# Amplifier_Right.net
KiCad netlist of a schematic drawn in Altium Designer
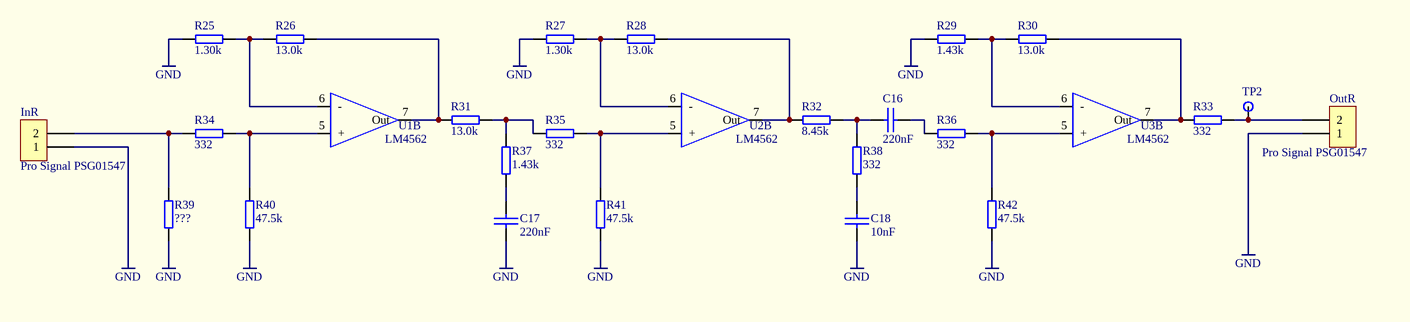
[diagram p0: Amplifier_Right.SchDoc]

(export (version "E")
  (design (tool "Eeschema 10.0.6"))
  (components
    (comp (ref "C16")
      (value "220nF")
      (footprint "CAP_C200-1")
      (description "Capacitor")
      (libsource (lib "*") (part "CAP"))
    )
    (comp (ref "C17")
      (value "220nF")
      (footprint "CAP_C200-1")
      (description "Capacitor")
      (libsource (lib "*") (part "CAP"))
    )
    (comp (ref "C18")
      (value "10nF")
      (footprint "CAP_C200")
      (description "Capacitor")
      (libsource (lib "*") (part "CAP"))
    )
    (comp (ref "InR")
      (value "Pro Signal PSG01547")
      (footprint "CON_RCA_PSG01547")
      (description "Connector")
      (libsource (lib "*") (part "CON2"))
    )
    (comp (ref "OutR")
      (value "Pro Signal PSG01547")
      (footprint "CON_RCA_PSG01547")
      (description "Connector")
      (libsource (lib "") (part "CON2_1"))
    )
    (comp (ref "R25")
      (value "1.30k")
      (footprint "RES_R400")
      (description "Resistor")
      (libsource (lib "MainSchlib") (part "RES"))
    )
    (comp (ref "R26")
      (value "13.0k")
      (footprint "RES_R400")
      (description "Resistor")
      (libsource (lib "MainSchlib") (part "RES"))
    )
    (comp (ref "R27")
      (value "1.30k")
      (footprint "RES_R400")
      (description "Resistor")
      (libsource (lib "MainSchlib") (part "RES"))
    )
    (comp (ref "R28")
      (value "13.0k")
      (footprint "RES_R400")
      (description "Resistor")
      (libsource (lib "MainSchlib") (part "RES"))
    )
    (comp (ref "R29")
      (value "1.43k")
      (footprint "RES_R400")
      (description "Resistor")
      (libsource (lib "MainSchlib") (part "RES"))
    )
    (comp (ref "R30")
      (value "13.0k")
      (footprint "RES_R400")
      (description "Resistor")
      (libsource (lib "MainSchlib") (part "RES"))
    )
    (comp (ref "R31")
      (value "13.0k")
      (footprint "RES_R400")
      (description "Resistor")
      (libsource (lib "MainSchlib") (part "RES"))
    )
    (comp (ref "R32")
      (value "8.45k")
      (footprint "RES_R400")
      (description "Resistor")
      (libsource (lib "MainSchlib") (part "RES"))
    )
    (comp (ref "R33")
      (value "332")
      (footprint "RES_R400")
      (description "Resistor")
      (libsource (lib "MainSchlib") (part "RES"))
    )
    (comp (ref "R34")
      (value "332")
      (footprint "RES_R400")
      (description "Resistor")
      (libsource (lib "MainSchlib") (part "RES"))
    )
    (comp (ref "R35")
      (value "332")
      (footprint "RES_R400")
      (description "Resistor")
      (libsource (lib "MainSchlib") (part "RES"))
    )
    (comp (ref "R36")
      (value "332")
      (footprint "RES_R400")
      (description "Resistor")
      (libsource (lib "MainSchlib") (part "RES"))
    )
    (comp (ref "R37")
      (value "1.43k")
      (footprint "RES_R400")
      (description "Resistor")
      (libsource (lib "MainSchlib") (part "RES"))
    )
    (comp (ref "R38")
      (value "332")
      (footprint "RES_R400")
      (description "Resistor")
      (libsource (lib "MainSchlib") (part "RES"))
    )
    (comp (ref "R39")
      (value "???")
      (footprint "RES_R400")
      (description "Resistor")
      (libsource (lib "MainSchlib") (part "RES"))
    )
    (comp (ref "R40")
      (value "47.5k")
      (footprint "RES_R400")
      (description "Resistor")
      (libsource (lib "MainSchlib") (part "RES"))
    )
    (comp (ref "R41")
      (value "47.5k")
      (footprint "RES_R400")
      (description "Resistor")
      (libsource (lib "MainSchlib") (part "RES"))
    )
    (comp (ref "R42")
      (value "47.5k")
      (footprint "RES_R400")
      (description "Resistor")
      (libsource (lib "MainSchlib") (part "RES"))
    )
    (comp (ref "TP2")
      (value "TESTPAD")
      (footprint "MISC_PAD-36/65")
      (libsource (lib "MainSchlib") (part "TESTPAD"))
    )
    (comp (ref "U1")
      (value "LM4562")
      (footprint "IC_DIP-8")
      (description "standard dual op-amp")
      (libsource (lib "MainSchlib") (part "OPAMP_Dual"))
    )
    (comp (ref "U2")
      (value "LM4562")
      (footprint "IC_DIP-8")
      (description "standard dual op-amp")
      (libsource (lib "MainSchlib") (part "OPAMP_Dual"))
    )
    (comp (ref "U3")
      (value "LM4562")
      (footprint "IC_DIP-8")
      (description "standard dual op-amp")
      (libsource (lib "MainSchlib") (part "OPAMP_Dual"))
    )
  )
  (nets
    (net (code "1") (name "GND") (class "Default")
      (node (ref "C17") (pin "2") (pinfunction "2_2") (pintype "passive"))
      (node (ref "C18") (pin "2") (pinfunction "2_2") (pintype "passive"))
      (node (ref "InR") (pin "1") (pinfunction "1_1") (pintype "passive"))
      (node (ref "OutR") (pin "1") (pinfunction "1_1") (pintype "passive"))
      (node (ref "R25") (pin "2") (pintype "passive"))
      (node (ref "R27") (pin "2") (pintype "passive"))
      (node (ref "R29") (pin "2") (pintype "passive"))
      (node (ref "R39") (pin "1") (pintype "passive"))
      (node (ref "R40") (pin "2") (pintype "passive"))
      (node (ref "R41") (pin "2") (pintype "passive"))
      (node (ref "R42") (pin "2") (pintype "passive"))
    )
    (net (code "2") (name "Net-(C16-Pad1)") (class "Default")
      (node (ref "C16") (pin "1") (pinfunction "1_1") (pintype "passive"))
      (node (ref "R32") (pin "1") (pintype "passive"))
      (node (ref "R38") (pin "1") (pintype "passive"))
    )
    (net (code "3") (name "Net-(C16-Pad2)") (class "Default")
      (node (ref "C16") (pin "2") (pinfunction "2_2") (pintype "passive"))
      (node (ref "R36") (pin "2") (pintype "passive"))
    )
    (net (code "4") (name "Net-(C17-Pad1)") (class "Default")
      (node (ref "C17") (pin "1") (pinfunction "1_1") (pintype "passive"))
      (node (ref "R37") (pin "2") (pintype "passive"))
    )
    (net (code "5") (name "Net-(C18-Pad1)") (class "Default")
      (node (ref "C18") (pin "1") (pinfunction "1_1") (pintype "passive"))
      (node (ref "R38") (pin "2") (pintype "passive"))
    )
    (net (code "6") (name "Net-(InR-Pad2)") (class "Default")
      (node (ref "InR") (pin "2") (pinfunction "2_2") (pintype "passive"))
      (node (ref "R34") (pin "2") (pintype "passive"))
      (node (ref "R39") (pin "2") (pintype "passive"))
    )
    (net (code "7") (name "Net-(OutR-Pad2)") (class "Default")
      (node (ref "OutR") (pin "2") (pinfunction "2_2") (pintype "passive"))
      (node (ref "R33") (pin "1") (pintype "passive"))
      (node (ref "TP2") (pin "1") (pinfunction "1_1") (pintype "passive"))
    )
    (net (code "8") (name "Net-(R31-Pad1)") (class "Default")
      (node (ref "R31") (pin "1") (pintype "passive"))
      (node (ref "R35") (pin "2") (pintype "passive"))
      (node (ref "R37") (pin "1") (pintype "passive"))
    )
    (net (code "9") (name "Net-(U1B-+)") (class "Default")
      (node (ref "R34") (pin "1") (pintype "passive"))
      (node (ref "R40") (pin "1") (pintype "passive"))
      (node (ref "U1") (pin "5") (pinfunction "+_5") (pintype "passive"))
    )
    (net (code "10") (name "Net-(U1B--)") (class "Default")
      (node (ref "R25") (pin "1") (pintype "passive"))
      (node (ref "R26") (pin "2") (pintype "passive"))
      (node (ref "U1") (pin "6") (pinfunction "-_6") (pintype "passive"))
    )
    (net (code "11") (name "Net-(U1B-Out)") (class "Default")
      (node (ref "R26") (pin "1") (pintype "passive"))
      (node (ref "R31") (pin "2") (pintype "passive"))
      (node (ref "U1") (pin "7") (pinfunction "Out_7") (pintype "passive"))
    )
    (net (code "12") (name "Net-(U2B-+)") (class "Default")
      (node (ref "R35") (pin "1") (pintype "passive"))
      (node (ref "R41") (pin "1") (pintype "passive"))
      (node (ref "U2") (pin "5") (pinfunction "+_5") (pintype "passive"))
    )
    (net (code "13") (name "Net-(U2B--)") (class "Default")
      (node (ref "R27") (pin "1") (pintype "passive"))
      (node (ref "R28") (pin "2") (pintype "passive"))
      (node (ref "U2") (pin "6") (pinfunction "-_6") (pintype "passive"))
    )
    (net (code "14") (name "Net-(U2B-Out)") (class "Default")
      (node (ref "R28") (pin "1") (pintype "passive"))
      (node (ref "R32") (pin "2") (pintype "passive"))
      (node (ref "U2") (pin "7") (pinfunction "Out_7") (pintype "passive"))
    )
    (net (code "15") (name "Net-(U3B-+)") (class "Default")
      (node (ref "R36") (pin "1") (pintype "passive"))
      (node (ref "R42") (pin "1") (pintype "passive"))
      (node (ref "U3") (pin "5") (pinfunction "+_5") (pintype "passive"))
    )
    (net (code "16") (name "Net-(U3B--)") (class "Default")
      (node (ref "R29") (pin "1") (pintype "passive"))
      (node (ref "R30") (pin "2") (pintype "passive"))
      (node (ref "U3") (pin "6") (pinfunction "-_6") (pintype "passive"))
    )
    (net (code "17") (name "Net-(U3B-Out)") (class "Default")
      (node (ref "R30") (pin "1") (pintype "passive"))
      (node (ref "R33") (pin "2") (pintype "passive"))
      (node (ref "U3") (pin "7") (pinfunction "Out_7") (pintype "passive"))
    )
  )
)
